# Peggy_Tracker.net
KiCad netlist of a schematic drawn in Altium Designer
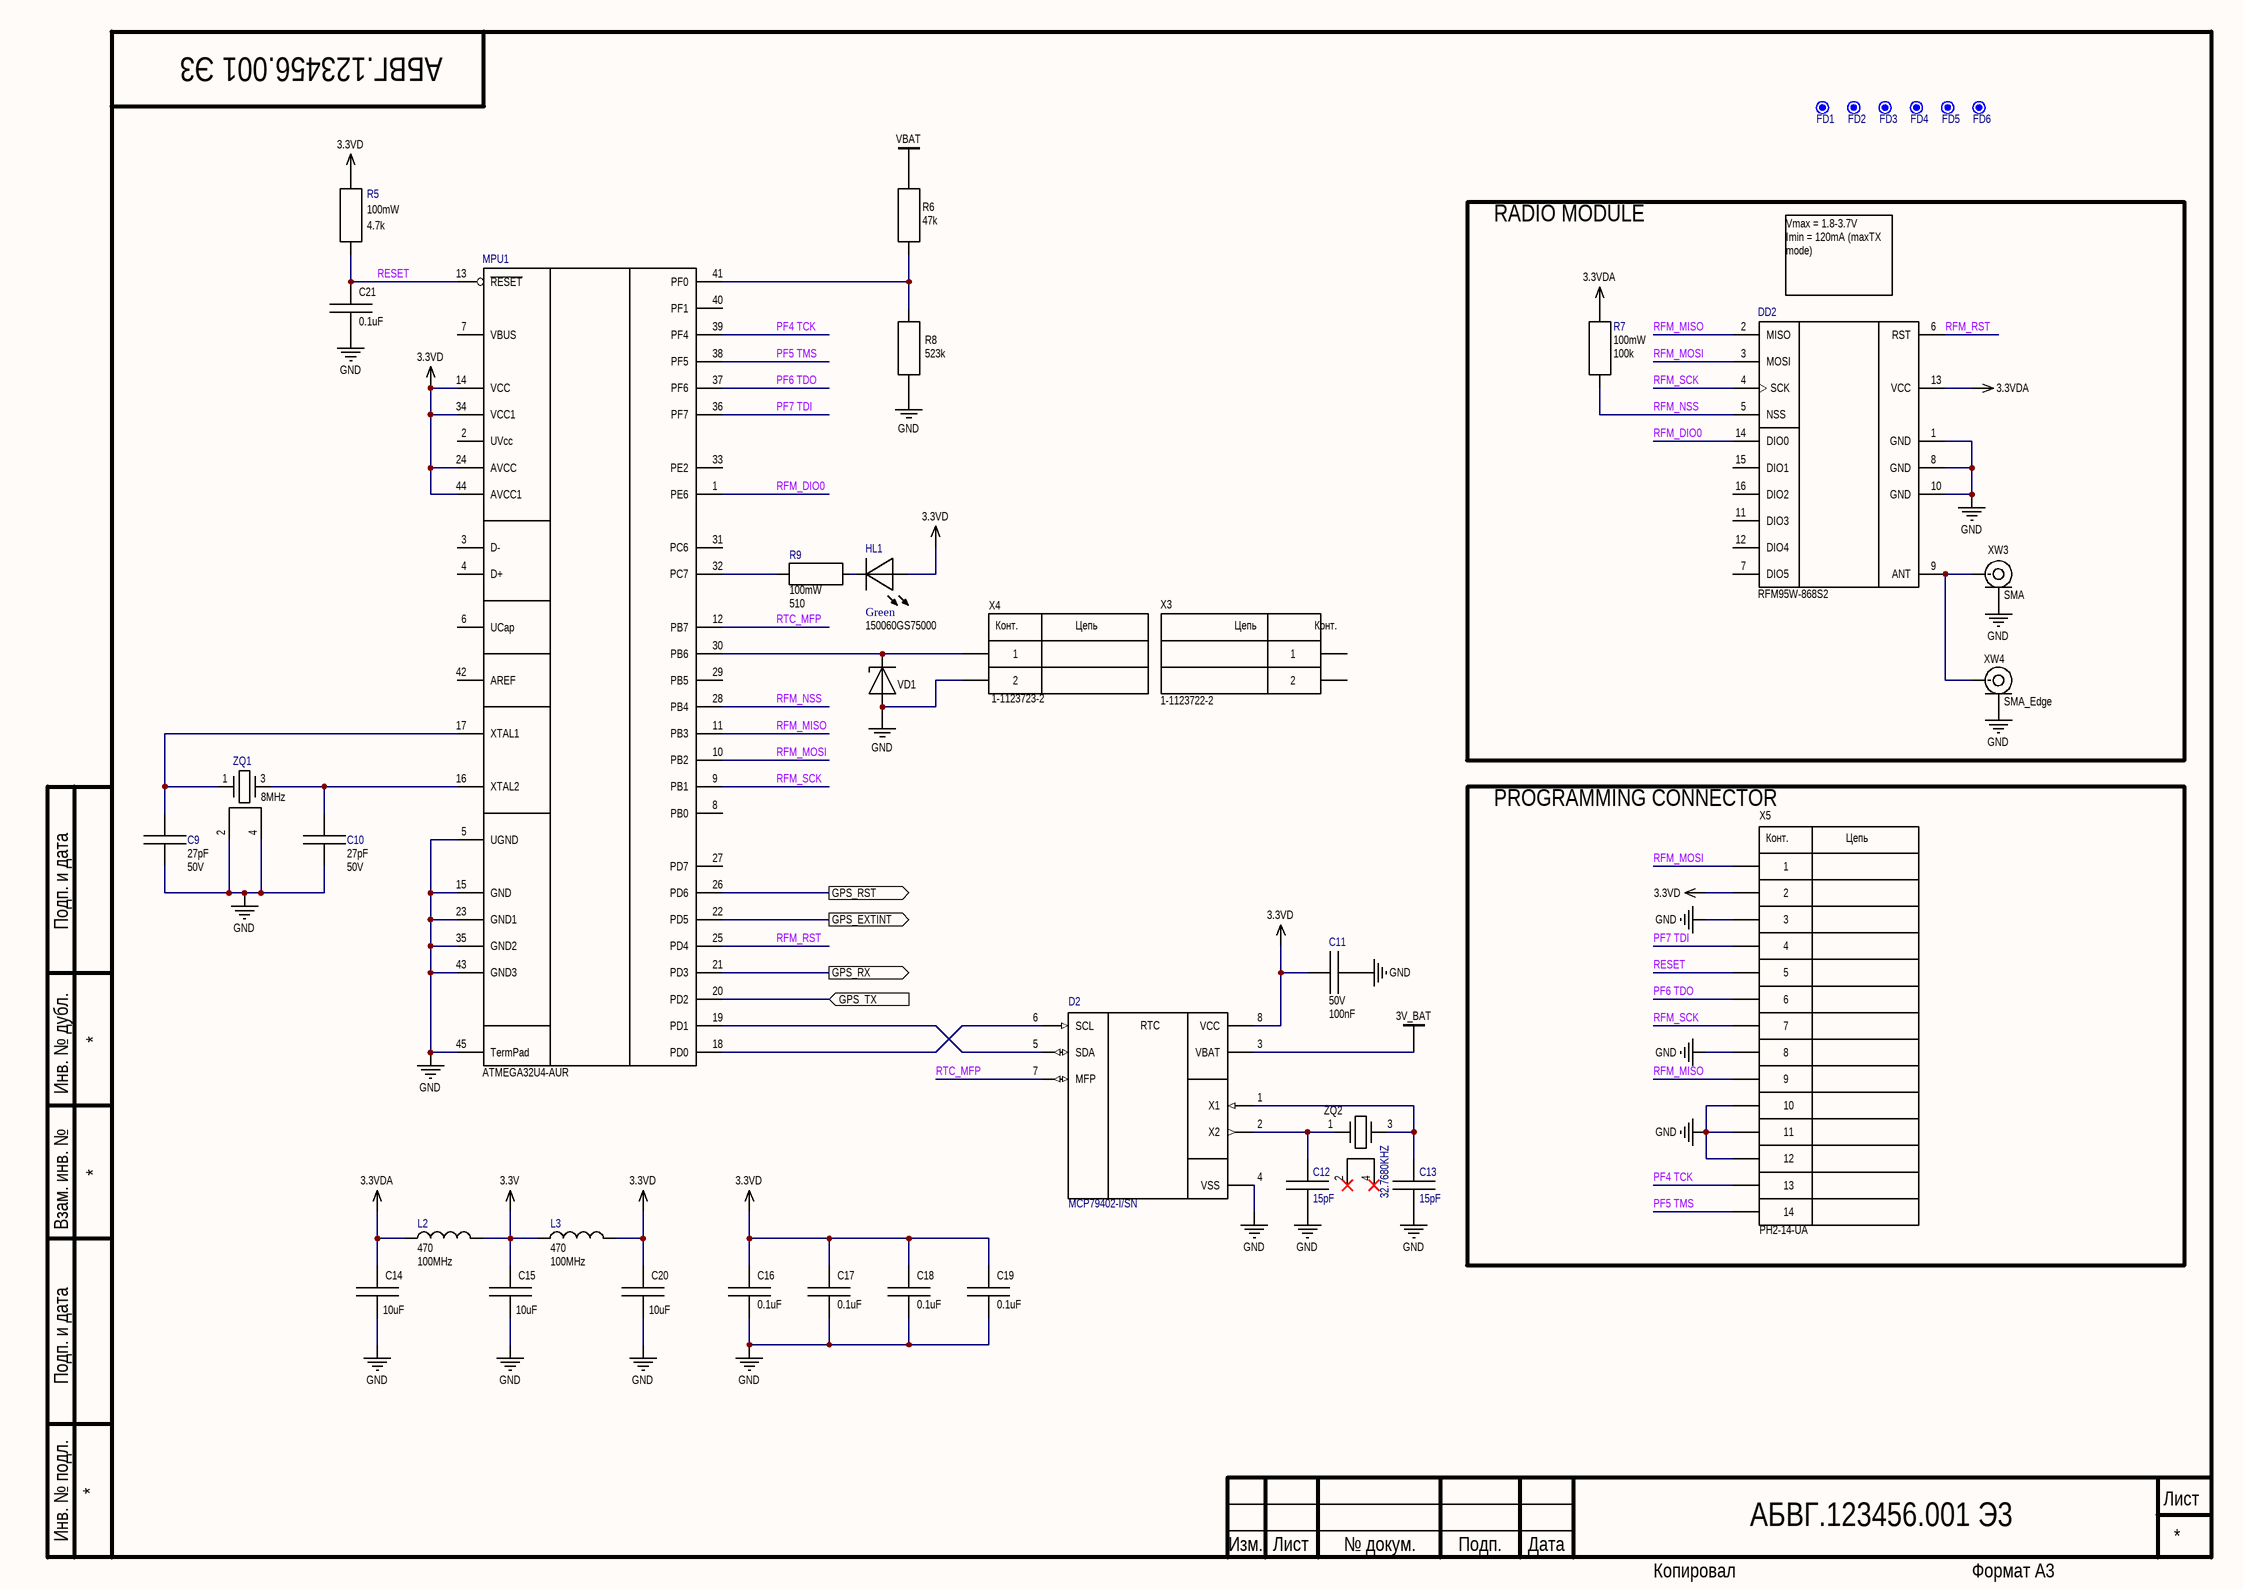
[diagram p0: Схема блока МК Peggy Tracker.SchDoc]

(export (version "E")
  (design (tool "Eeschema 10.0.6"))
  (components
    (comp (ref "C9")
      (value "CC0603JPNPO9BN270")
      (footprint "CAPC1608X87X35NL15T15")
      (description "0603 50V C0G 27pF 5% multilayer ceramic capacitor")
      (fields
        (field (name "MANUFACTURER") "YAGEO")
        (field (name "CAPACITANCE") "27pF")
        (field (name "VOLTAGE RATING") "50V")
        (field (name "TOLERANCE") "5%")
      )
      (libsource (lib "Sergek Concord Server") (part "CAP-NP-2"))
    )
    (comp (ref "C10")
      (value "CC0603JPNPO9BN270")
      (footprint "CAPC1608X87X35NL15T15")
      (description "0603 50V C0G 27pF 5% multilayer ceramic capacitor")
      (fields
        (field (name "MANUFACTURER") "YAGEO")
        (field (name "CAPACITANCE") "27pF")
        (field (name "VOLTAGE RATING") "50V")
        (field (name "TOLERANCE") "5%")
      )
      (libsource (lib "Sergek Concord Server") (part "CAP-NP-2"))
    )
    (comp (ref "C11")
      (value "100nF")
      (footprint "CAPC1608X09N")
      (description "CAP CER 0.1UF 50V X7R 0603")
      (fields
        (field (name "VOLTAGE RATING") "50V")
        (field (name "MANUFACTURER") "Murata")
        (field (name "MANUFACTURER PART NUMBER") "GCM188R71H104KA57D")
        (field (name "SOURCE") "Meteo_1.SCHLIB")
      )
      (libsource (lib "Sergek Concord Server") (part "CAP-NP-2"))
    )
    (comp (ref "C12")
      (value "15pF")
      (footprint "standard:CH0603C")
      (description "CAP CER 15PF 50V C0G/NPO 0603")
      (fields (field (name "MANUFACTURER") "YAGEO"))
      (libsource (lib "Discrete") (part "Capacitor"))
    )
    (comp (ref "C13")
      (value "15pF")
      (footprint "standard:CH0603C")
      (description "CAP CER 15PF 50V C0G/NPO 0603")
      (fields (field (name "MANUFACTURER") "YAGEO"))
      (libsource (lib "Discrete") (part "Capacitor"))
    )
    (comp (ref "C14")
      (value "10uF")
      (footprint "standard:CH1206C")
      (description "CAP CER 10UF 16V X7R 1206")
      (fields (field (name "MANUFACTURER") "Murata Electronics"))
      (libsource (lib "Discrete") (part "Capacitor"))
    )
    (comp (ref "C15")
      (value "10uF")
      (footprint "standard:CH1206C")
      (description "CAP CER 10UF 16V X7R 1206")
      (fields (field (name "MANUFACTURER") "Murata Electronics"))
      (libsource (lib "Discrete") (part "Capacitor"))
    )
    (comp (ref "C16")
      (value "0.1uF")
      (footprint "CH0603C")
      (fields (field (name "MANUFACTURER") "Murata Electronics"))
      (libsource (lib "Discrete") (part "Capacitor"))
    )
    (comp (ref "C17")
      (value "0.1uF")
      (footprint "CH0603C")
      (fields (field (name "MANUFACTURER") "Murata Electronics"))
      (libsource (lib "Discrete") (part "Capacitor"))
    )
    (comp (ref "C18")
      (value "0.1uF")
      (footprint "CH0603C")
      (fields (field (name "MANUFACTURER") "Murata Electronics"))
      (libsource (lib "Discrete") (part "Capacitor"))
    )
    (comp (ref "C19")
      (value "0.1uF")
      (footprint "CH0603C")
      (fields (field (name "MANUFACTURER") "Murata Electronics"))
      (libsource (lib "Discrete") (part "Capacitor"))
    )
    (comp (ref "C20")
      (value "10uF")
      (footprint "standard:CH1206C")
      (description "CAP CER 10UF 16V X7R 1206")
      (fields (field (name "MANUFACTURER") "Murata Electronics"))
      (libsource (lib "Discrete") (part "Capacitor"))
    )
    (comp (ref "C21")
      (value "0.1uF")
      (footprint "CH0603C")
      (fields (field (name "MANUFACTURER") "Murata Electronics"))
      (libsource (lib "Discrete") (part "Capacitor"))
    )
    (comp (ref "D2")
      (value "MCP79402-I/SN")
      (footprint "standard:8-SOIC")
      (description "RTC")
      (fields (field (name "MANUFACTURER") "Microchip Technology"))
      (libsource (lib "Analog") (part "MCP7940M-I/SN"))
    )
    (comp (ref "DD2")
      (value "RFM95W-868S2")
      (footprint "RFM95W-868S2")
      (description "RF TXRX MODULE ISM<1GHZ")
      (fields
        (field (name "MANUFACTURER") "RF Solutions")
        (field (name "MANUFACTURER PART NUMBER") "RFM95W-868S2")
      )
      (libsource (lib "Sergek Concord Server") (part "HPD13A (RFM95)"))
    )
    (comp (ref "FD1")
      (value "FID1X2R")
      (footprint "FID1X2R")
      (description "Fiducial - Round 1x2mm")
      (libsource (lib "Sergek Concord Server") (part "CMP-00134-2"))
    )
    (comp (ref "FD2")
      (value "FID1X2R")
      (footprint "FID1X2R")
      (description "Fiducial - Round 1x2mm")
      (libsource (lib "Sergek Concord Server") (part "CMP-00134-2"))
    )
    (comp (ref "FD3")
      (value "FID1X2R")
      (footprint "FID1X2R")
      (description "Fiducial - Round 1x2mm")
      (libsource (lib "Sergek Concord Server") (part "CMP-00134-2"))
    )
    (comp (ref "FD4")
      (value "FID1X2R")
      (footprint "FID1X2R")
      (description "Fiducial - Round 1x2mm")
      (libsource (lib "Sergek Concord Server") (part "CMP-00134-2"))
    )
    (comp (ref "FD5")
      (value "FID1X2R")
      (footprint "FID1X2R")
      (description "Fiducial - Round 1x2mm")
      (libsource (lib "Sergek Concord Server") (part "CMP-00134-2"))
    )
    (comp (ref "FD6")
      (value "FID1X2R")
      (footprint "FID1X2R")
      (description "Fiducial - Round 1x2mm")
      (libsource (lib "Sergek Concord Server") (part "CMP-00134-2"))
    )
    (comp (ref "HL1")
      (value "150060GS75000")
      (footprint "CH0603LG")
      (description "WURTH ELEKTRONIK - 150060GS75000 - LED, Green, 520 nm, 3.2 V, 30 mA, 430 mcd RoHS Compliant: Yes")
      (fields
        (field (name "COLOR") "Green")
        (field (name "MANUFACTURER PART NUMBER") "150060GS75000")
        (field (name "MANUFACTURER") "Würth Elektronik")
      )
      (libsource (lib "Sergek Concord Server") (part "Symbol"))
    )
    (comp (ref "L2")
      (value "MH2029-471Y")
      (footprint "MH2029-471Y-Footprint-1")
      (description "Ferrite Beads High Current Chip 470Ohm 25% 100MHz 1A 0.2Ohm DCR 0805 T/R")
      (fields
        (field (name "TOLERANCE") "25%")
        (field (name "IMPEDANCE") "470")
        (field (name "TEST FREQUENCY") "100MHz")
        (field (name "MANUFACTURER") "Bourns Inc.")
      )
      (libsource (lib "Sergek Concord Server") (part "IND-2"))
    )
    (comp (ref "L3")
      (value "MH2029-471Y")
      (footprint "MH2029-471Y-Footprint-1")
      (description "Ferrite Beads High Current Chip 470Ohm 25% 100MHz 1A 0.2Ohm DCR 0805 T/R")
      (fields
        (field (name "TOLERANCE") "25%")
        (field (name "IMPEDANCE") "470")
        (field (name "TEST FREQUENCY") "100MHz")
        (field (name "MANUFACTURER") "Bourns Inc.")
      )
      (libsource (lib "Sergek Concord Server") (part "IND-2"))
    )
    (comp (ref "MPU1")
      (value "ATMEGA32U4-AU")
      (footprint "ATMEGA32U4-MU")
      (fields
        (field (name "MANUFACTURER PART NUMBER") "ATMEGA32U4-AUR")
        (field (name "MANUFACTURER") "Atmel")
      )
      (libsource (lib "Sergek Concord Server") (part "ATMEGA32U4-AU"))
    )
    (comp (ref "R5")
      (value "RMCF0603FT4K70")
      (footprint "CH0603R")
      (description "Res Thick Film 0603 4.7K Ohm 1% 1/10W 100ppm/C Molded SMD SMD Paper T/R")
      (fields
        (field (name "TOLERANCE") "1%")
        (field (name "POWER RATING") "100mW")
        (field (name "RESISTANCE") "4.7k")
        (field (name "MANUFACTURER") "Stackpole Electronics Inc")
      )
      (libsource (lib "Sergek Concord Server") (part "RES-2"))
    )
    (comp (ref "R6")
      (value "47k")
      (footprint "standard:CH0603R")
      (fields (field (name "MANUFACTURER") "YAGEO"))
      (libsource (lib "Discrete") (part "Resistor"))
    )
    (comp (ref "R7")
      (value "100k")
      (footprint "RESC1608X55X25NL10T15")
      (description "Chip Resistor, 100 KOhm, +/- 1%, 0.1 W, -55 to 155 degC, 0603 (1608 Metric)")
      (fields
        (field (name "POWER") "100mW")
        (field (name "TOLERANCE") "1%")
        (field (name "Comment") "Resistor 100k +/-1% 0603 100 mW")
      )
      (libsource (lib "Sergek Concord Server") (part "RES-2"))
    )
    (comp (ref "R8")
      (value "523k")
      (footprint "standard:CH0603R")
      (fields (field (name "MANUFACTURER") "YAGEO"))
      (libsource (lib "Discrete") (part "Resistor"))
    )
    (comp (ref "R9")
      (value "RMCF0603JT510R")
      (footprint "RESC1608X55X25NL10T15")
      (description "510 Ohms ±5% 0.1W, 1/10W Chip Resistor 0603 (1608 Metric) Automotive AEC-Q200 Thick Film")
      (fields
        (field (name "MANUFACTURER") "Stackpole Electronics Inc")
        (field (name "POWER RATING") "100mW")
        (field (name "RESISTANCE") "510")
        (field (name "TOLERANCE") "5%")
      )
      (libsource (lib "") (part "RES-2_1"))
    )
    (comp (ref "VD1")
      (value "DESD3V3S1BL-7B")
      (footprint "X1-DFN1006-2 (0402 )")
      (fields (field (name "MANUFACTURER") "Diodes Incorporated"))
      (libsource (lib "Diods") (part "Diod Zener"))
    )
    (comp (ref "X3")
      (value "1-1123722-2")
      (footprint "CON: 1-1123723-2")
      (description "CONN PLUG HOUSING EP .156 2POS")
      (fields (field (name "MANUFACTURER") "TE Connectivity AMP Connectors"))
      (libsource (lib "Connectors") (part "2-Connector"))
    )
    (comp (ref "X4")
      (value "1-1123723-2")
      (footprint "CON: 1-1123723-2")
      (description "CONN HEADER VERT 2POS 3.96MM")
      (fields (field (name "MANUFACTURER") "TE Connectivity AMP Connectors"))
      (libsource (lib "") (part "2-Connector_1"))
    )
    (comp (ref "X5")
      (value "PH2-14-UA")
      (footprint "custom:CON: PLD-14")
      (description "CONN HEADER VERT 14POS 2.54MM")
      (fields (field (name "MANUFACTURER") "Adam Tech"))
      (libsource (lib "Connectors") (part "14-Connector"))
    )
    (comp (ref "XW3")
      (value "SMA")
      (footprint "custom:CON: SMA")
      (description "CONN SMA RCPT STR 50 OHM PCB")
      (fields (field (name "MANUFACTURER") "Molex"))
      (libsource (lib "Connectors") (part "SMA"))
    )
    (comp (ref "XW4")
      (value "SMA_Edge")
      (footprint "CON: SMA - Edge")
      (description "RF")
      (fields (field (name "MANUFACTURER") "Molex"))
      (libsource (lib "Connectors") (part "SMA"))
    )
    (comp (ref "ZQ1")
      (value "FY0800018")
      (footprint "FY0800018-Footprint-1")
      (description "Crystal 8MHz ±30ppm (Tol) ±30ppm (Stability) 18pF FUND 100Ohm 4-Pin SMD T/R")
      (fields (field (name "MANUFACTURER") "Diodes Incorporated") (field (name "FREQUENCY") "8MHz"))
      (libsource (lib "Sergek Concord Server") (part "XTAL-2"))
    )
    (comp (ref "ZQ2")
      (value "32.7680KHZ")
      (footprint "custom:OSC: 3215")
      (fields (field (name "MANUFACTURER") "Abracon LLC"))
      (libsource (lib "Discrete") (part "Oscillator"))
    )
  )
  (nets
    (net (code "1") (name "/GPS_EXTINT") (class "Default")
      (node (ref "MPU1") (pin "22") (pinfunction "PD5_22") (pintype "passive"))
    )
    (net (code "2") (name "/GPS_RST") (class "Default")
      (node (ref "MPU1") (pin "26") (pinfunction "PD6_26") (pintype "passive"))
    )
    (net (code "3") (name "/GPS_RX") (class "Default")
      (node (ref "MPU1") (pin "21") (pinfunction "PD3_21") (pintype "passive"))
    )
    (net (code "4") (name "/GPS_TX") (class "Default")
      (node (ref "MPU1") (pin "20") (pinfunction "PD2_20") (pintype "passive"))
    )
    (net (code "5") (name "/PF4 TCK") (class "Default")
      (node (ref "MPU1") (pin "39") (pinfunction "PF4_39") (pintype "passive"))
      (node (ref "X5") (pin "13") (pinfunction "13_13") (pintype "power_in"))
    )
    (net (code "6") (name "/PF5 TMS") (class "Default")
      (node (ref "MPU1") (pin "38") (pinfunction "PF5_38") (pintype "passive"))
      (node (ref "X5") (pin "14") (pinfunction "14_14") (pintype "power_in"))
    )
    (net (code "7") (name "/PF6 TDO") (class "Default")
      (node (ref "MPU1") (pin "37") (pinfunction "PF6_37") (pintype "passive"))
      (node (ref "X5") (pin "6") (pinfunction "6_6") (pintype "passive"))
    )
    (net (code "8") (name "/PF7 TDI") (class "Default")
      (node (ref "MPU1") (pin "36") (pinfunction "PF7_36") (pintype "passive"))
      (node (ref "X5") (pin "4") (pinfunction "4_4") (pintype "power_in"))
    )
    (net (code "9") (name "/RESET") (class "Default")
      (node (ref "C21") (pin "1") (pinfunction "1_1") (pintype "passive"))
      (node (ref "MPU1") (pin "13") (pinfunction "~{RESET}_13") (pintype "passive"))
      (node (ref "R5") (pin "1") (pinfunction "1_1") (pintype "passive"))
      (node (ref "X5") (pin "5") (pinfunction "5_5") (pintype "power_in"))
    )
    (net (code "10") (name "/RFM_DIO0") (class "Default")
      (node (ref "DD2") (pin "14") (pinfunction "DIO0_14") (pintype "passive"))
      (node (ref "MPU1") (pin "1") (pinfunction "PE6_1") (pintype "passive"))
    )
    (net (code "11") (name "/RFM_MISO") (class "Default")
      (node (ref "DD2") (pin "2") (pinfunction "MISO_2") (pintype "passive"))
      (node (ref "MPU1") (pin "11") (pinfunction "PB3_11") (pintype "passive"))
      (node (ref "X5") (pin "9") (pinfunction "9_9") (pintype "power_in"))
    )
    (net (code "12") (name "/RFM_MOSI") (class "Default")
      (node (ref "DD2") (pin "3") (pinfunction "MOSI_3") (pintype "passive"))
      (node (ref "MPU1") (pin "10") (pinfunction "PB2_10") (pintype "passive"))
      (node (ref "X5") (pin "1") (pinfunction "1_1") (pintype "passive"))
    )
    (net (code "13") (name "/RFM_NSS") (class "Default")
      (node (ref "DD2") (pin "5") (pinfunction "NSS_5") (pintype "passive"))
      (node (ref "MPU1") (pin "28") (pinfunction "PB4_28") (pintype "passive"))
      (node (ref "R7") (pin "1") (pinfunction "1_1") (pintype "passive"))
    )
    (net (code "14") (name "/RFM_RST") (class "Default")
      (node (ref "DD2") (pin "6") (pinfunction "RST_6") (pintype "passive"))
      (node (ref "MPU1") (pin "25") (pinfunction "PD4_25") (pintype "passive"))
    )
    (net (code "15") (name "/RFM_SCK") (class "Default")
      (node (ref "DD2") (pin "4") (pinfunction "SCK_4") (pintype "passive"))
      (node (ref "MPU1") (pin "9") (pinfunction "PB1_9") (pintype "passive"))
      (node (ref "X5") (pin "7") (pinfunction "7_7") (pintype "passive"))
    )
    (net (code "16") (name "/RTC_MFP") (class "Default")
      (node (ref "D2") (pin "7") (pinfunction "MFP_7") (pintype "bidirectional"))
      (node (ref "MPU1") (pin "12") (pinfunction "PB7_12") (pintype "passive"))
    )
    (net (code "17") (name "3.3V") (class "Default")
      (node (ref "C15") (pin "1") (pinfunction "1_1") (pintype "passive"))
      (node (ref "L2") (pin "2") (pinfunction "2_2") (pintype "passive"))
      (node (ref "L3") (pin "1") (pinfunction "1_1") (pintype "passive"))
    )
    (net (code "18") (name "3.3VD") (class "Default")
      (node (ref "C11") (pin "2") (pinfunction "2_2") (pintype "passive"))
      (node (ref "C16") (pin "1") (pinfunction "1_1") (pintype "passive"))
      (node (ref "C17") (pin "1") (pinfunction "1_1") (pintype "passive"))
      (node (ref "C18") (pin "1") (pinfunction "1_1") (pintype "passive"))
      (node (ref "C19") (pin "1") (pinfunction "1_1") (pintype "passive"))
      (node (ref "C20") (pin "1") (pinfunction "1_1") (pintype "passive"))
      (node (ref "D2") (pin "8") (pinfunction "VCC_8") (pintype "passive"))
      (node (ref "HL1") (pin "2") (pinfunction "2_2") (pintype "passive"))
      (node (ref "L3") (pin "2") (pinfunction "2_2") (pintype "passive"))
      (node (ref "MPU1") (pin "14") (pinfunction "VCC_14") (pintype "passive"))
      (node (ref "MPU1") (pin "24") (pinfunction "AVCC_24") (pintype "passive"))
      (node (ref "MPU1") (pin "34") (pinfunction "VCC1_34") (pintype "passive"))
      (node (ref "MPU1") (pin "44") (pinfunction "AVCC1_44") (pintype "passive"))
      (node (ref "R5") (pin "2") (pinfunction "2_2") (pintype "passive"))
      (node (ref "X5") (pin "2") (pinfunction "2_2") (pintype "passive"))
    )
    (net (code "19") (name "3.3VDA") (class "Default")
      (node (ref "C14") (pin "1") (pinfunction "1_1") (pintype "passive"))
      (node (ref "DD2") (pin "13") (pinfunction "VCC_13") (pintype "passive"))
      (node (ref "L2") (pin "1") (pinfunction "1_1") (pintype "passive"))
      (node (ref "R7") (pin "2") (pinfunction "2_2") (pintype "passive"))
    )
    (net (code "20") (name "3V_BAT") (class "Default")
      (node (ref "D2") (pin "3") (pinfunction "VBAT_3") (pintype "passive"))
    )
    (net (code "21") (name "GND") (class "Default")
      (node (ref "C10") (pin "1") (pinfunction "1_1") (pintype "passive"))
      (node (ref "C11") (pin "1") (pinfunction "1_1") (pintype "passive"))
      (node (ref "C12") (pin "2") (pinfunction "2_2") (pintype "passive"))
      (node (ref "C13") (pin "2") (pinfunction "2_2") (pintype "passive"))
      (node (ref "C14") (pin "2") (pinfunction "2_2") (pintype "passive"))
      (node (ref "C15") (pin "2") (pinfunction "2_2") (pintype "passive"))
      (node (ref "C16") (pin "2") (pinfunction "2_2") (pintype "passive"))
      (node (ref "C17") (pin "2") (pinfunction "2_2") (pintype "passive"))
      (node (ref "C18") (pin "2") (pinfunction "2_2") (pintype "passive"))
      (node (ref "C19") (pin "2") (pinfunction "2_2") (pintype "passive"))
      (node (ref "C20") (pin "2") (pinfunction "2_2") (pintype "passive"))
      (node (ref "C21") (pin "2") (pinfunction "2_2") (pintype "passive"))
      (node (ref "C9") (pin "1") (pinfunction "1_1") (pintype "passive"))
      (node (ref "D2") (pin "4") (pinfunction "VSS_4") (pintype "passive"))
      (node (ref "DD2") (pin "1") (pinfunction "GND_1") (pintype "passive"))
      (node (ref "DD2") (pin "10") (pinfunction "GND_10") (pintype "passive"))
      (node (ref "DD2") (pin "8") (pinfunction "GND_8") (pintype "passive"))
      (node (ref "MPU1") (pin "15") (pinfunction "GND_15") (pintype "passive"))
      (node (ref "MPU1") (pin "23") (pinfunction "GND1_23") (pintype "passive"))
      (node (ref "MPU1") (pin "35") (pinfunction "GND2_35") (pintype "passive"))
      (node (ref "MPU1") (pin "43") (pinfunction "GND3_43") (pintype "passive"))
      (node (ref "MPU1") (pin "45") (pinfunction "TermPad_45") (pintype "passive"))
      (node (ref "MPU1") (pin "5") (pinfunction "UGND_5") (pintype "passive"))
      (node (ref "R8") (pin "1") (pinfunction "1_1") (pintype "passive"))
      (node (ref "VD1") (pin "1") (pinfunction "A_1") (pintype "passive"))
      (node (ref "X4") (pin "2") (pinfunction "2_2") (pintype "passive"))
      (node (ref "X5") (pin "10") (pinfunction "10_10") (pintype "power_in"))
      (node (ref "X5") (pin "11") (pinfunction "11_11") (pintype "power_in"))
      (node (ref "X5") (pin "12") (pinfunction "12_12") (pintype "power_in"))
      (node (ref "X5") (pin "3") (pinfunction "3_3") (pintype "power_in"))
      (node (ref "X5") (pin "8") (pinfunction "8_8") (pintype "power_in"))
      (node (ref "XW3") (pin "2") (pinfunction "IN_2") (pintype "passive"))
      (node (ref "XW4") (pin "2") (pinfunction "IN_2") (pintype "passive"))
      (node (ref "ZQ1") (pin "2") (pinfunction "2_2") (pintype "passive"))
      (node (ref "ZQ1") (pin "4") (pinfunction "4_4") (pintype "passive"))
    )
    (net (code "22") (name "Net-(D2-SCL)") (class "Default")
      (node (ref "D2") (pin "6") (pinfunction "SCL_6") (pintype "input"))
      (node (ref "MPU1") (pin "18") (pinfunction "PD0_18") (pintype "passive"))
    )
    (net (code "23") (name "Net-(D2-SDA)") (class "Default")
      (node (ref "D2") (pin "5") (pinfunction "SDA_5") (pintype "bidirectional"))
      (node (ref "MPU1") (pin "19") (pinfunction "PD1_19") (pintype "passive"))
    )
    (net (code "24") (name "Net-(D2-X1)") (class "Default")
      (node (ref "C13") (pin "1") (pinfunction "1_1") (pintype "passive"))
      (node (ref "D2") (pin "1") (pinfunction "X1_1") (pintype "input"))
      (node (ref "ZQ2") (pin "3") (pinfunction "3_3") (pintype "passive"))
    )
    (net (code "25") (name "Net-(D2-X2)") (class "Default")
      (node (ref "C12") (pin "1") (pinfunction "1_1") (pintype "passive"))
      (node (ref "D2") (pin "2") (pinfunction "X2_2") (pintype "output"))
      (node (ref "ZQ2") (pin "1") (pinfunction "1_1") (pintype "passive"))
    )
    (net (code "26") (name "Net-(DD2-ANT)") (class "Default")
      (node (ref "DD2") (pin "9") (pinfunction "ANT_9") (pintype "passive"))
      (node (ref "XW3") (pin "1") (pinfunction "IN_1") (pintype "passive"))
      (node (ref "XW4") (pin "1") (pinfunction "IN_1") (pintype "passive"))
    )
    (net (code "27") (name "Net-(HL1-Pad1)") (class "Default")
      (node (ref "HL1") (pin "1") (pinfunction "1_1") (pintype "passive"))
      (node (ref "R9") (pin "2") (pinfunction "2_2") (pintype "passive"))
    )
    (net (code "28") (name "Net-(MPU1-PB6)") (class "Default")
      (node (ref "MPU1") (pin "30") (pinfunction "PB6_30") (pintype "passive"))
      (node (ref "VD1") (pin "2") (pinfunction "C_2") (pintype "passive"))
      (node (ref "X4") (pin "1") (pinfunction "1_1") (pintype "passive"))
    )
    (net (code "29") (name "Net-(MPU1-PC7)") (class "Default")
      (node (ref "MPU1") (pin "32") (pinfunction "PC7_32") (pintype "passive"))
      (node (ref "R9") (pin "1") (pinfunction "1_1") (pintype "passive"))
    )
    (net (code "30") (name "Net-(MPU1-PF0)") (class "Default")
      (node (ref "MPU1") (pin "41") (pinfunction "PF0_41") (pintype "passive"))
      (node (ref "R6") (pin "1") (pinfunction "1_1") (pintype "passive"))
      (node (ref "R8") (pin "2") (pinfunction "2_2") (pintype "passive"))
    )
    (net (code "31") (name "Net-(MPU1-XTAL1)") (class "Default")
      (node (ref "C9") (pin "2") (pinfunction "2_2") (pintype "passive"))
      (node (ref "MPU1") (pin "17") (pinfunction "XTAL1_17") (pintype "passive"))
      (node (ref "ZQ1") (pin "1") (pinfunction "1_1") (pintype "passive"))
    )
    (net (code "32") (name "Net-(MPU1-XTAL2)") (class "Default")
      (node (ref "C10") (pin "2") (pinfunction "2_2") (pintype "passive"))
      (node (ref "MPU1") (pin "16") (pinfunction "XTAL2_16") (pintype "passive"))
      (node (ref "ZQ1") (pin "3") (pinfunction "3_3") (pintype "passive"))
    )
    (net (code "33") (name "VBAT") (class "Default")
      (node (ref "R6") (pin "2") (pinfunction "2_2") (pintype "passive"))
    )
    (net (code "34") (name "unconnected-(DD2-DIO1-Pad15)") (class "Default")
      (node (ref "DD2") (pin "15") (pinfunction "DIO1_15") (pintype "passive"))
    )
    (net (code "35") (name "unconnected-(DD2-DIO2-Pad16)") (class "Default")
      (node (ref "DD2") (pin "16") (pinfunction "DIO2_16") (pintype "passive"))
    )
    (net (code "36") (name "unconnected-(DD2-DIO3-Pad11)") (class "Default")
      (node (ref "DD2") (pin "11") (pinfunction "DIO3_11") (pintype "passive"))
    )
    (net (code "37") (name "unconnected-(DD2-DIO4-Pad12)") (class "Default")
      (node (ref "DD2") (pin "12") (pinfunction "DIO4_12") (pintype "passive"))
    )
    (net (code "38") (name "unconnected-(DD2-DIO5-Pad7)") (class "Default")
      (node (ref "DD2") (pin "7") (pinfunction "DIO5_7") (pintype "passive"))
    )
    (net (code "39") (name "unconnected-(MPU1-AREF-Pad42)") (class "Default")
      (node (ref "MPU1") (pin "42") (pinfunction "AREF_42") (pintype "passive"))
    )
    (net (code "40") (name "unconnected-(MPU1-D+-Pad4)") (class "Default")
      (node (ref "MPU1") (pin "4") (pinfunction "D+_4") (pintype "passive"))
    )
    (net (code "41") (name "unconnected-(MPU1-D--Pad3)") (class "Default")
      (node (ref "MPU1") (pin "3") (pinfunction "D-_3") (pintype "passive"))
    )
    (net (code "42") (name "unconnected-(MPU1-PB0-Pad8)") (class "Default")
      (node (ref "MPU1") (pin "8") (pinfunction "PB0_8") (pintype "passive"))
    )
    (net (code "43") (name "unconnected-(MPU1-PB5-Pad29)") (class "Default")
      (node (ref "MPU1") (pin "29") (pinfunction "PB5_29") (pintype "passive"))
    )
    (net (code "44") (name "unconnected-(MPU1-PC6-Pad31)") (class "Default")
      (node (ref "MPU1") (pin "31") (pinfunction "PC6_31") (pintype "passive"))
    )
    (net (code "45") (name "unconnected-(MPU1-PD7-Pad27)") (class "Default")
      (node (ref "MPU1") (pin "27") (pinfunction "PD7_27") (pintype "passive"))
    )
    (net (code "46") (name "unconnected-(MPU1-PE2-Pad33)") (class "Default")
      (node (ref "MPU1") (pin "33") (pinfunction "PE2_33") (pintype "passive"))
    )
    (net (code "47") (name "unconnected-(MPU1-PF1-Pad40)") (class "Default")
      (node (ref "MPU1") (pin "40") (pinfunction "PF1_40") (pintype "passive"))
    )
    (net (code "48") (name "unconnected-(MPU1-UCap-Pad6)") (class "Default")
      (node (ref "MPU1") (pin "6") (pinfunction "UCap_6") (pintype "passive"))
    )
    (net (code "49") (name "unconnected-(MPU1-UVcc-Pad2)") (class "Default")
      (node (ref "MPU1") (pin "2") (pinfunction "UVcc_2") (pintype "passive"))
    )
    (net (code "50") (name "unconnected-(MPU1-VBUS-Pad7)") (class "Default")
      (node (ref "MPU1") (pin "7") (pinfunction "VBUS_7") (pintype "passive"))
    )
    (net (code "51") (name "unconnected-(X3-Pad1)") (class "Default")
      (node (ref "X3") (pin "1") (pinfunction "1_1") (pintype "passive"))
    )
    (net (code "52") (name "unconnected-(X3-Pad2)") (class "Default")
      (node (ref "X3") (pin "2") (pinfunction "2_2") (pintype "passive"))
    )
    (net (code "53") (name "unconnected-(ZQ2-Pad2)") (class "Default")
      (node (ref "ZQ2") (pin "2") (pinfunction "2_2") (pintype "passive+no_connect"))
    )
    (net (code "54") (name "unconnected-(ZQ2-Pad4)") (class "Default")
      (node (ref "ZQ2") (pin "4") (pinfunction "4_4") (pintype "passive+no_connect"))
    )
  )
)
